# MorsePlay_schematic.net
KiCad netlist of a schematic drawn in EAGLE
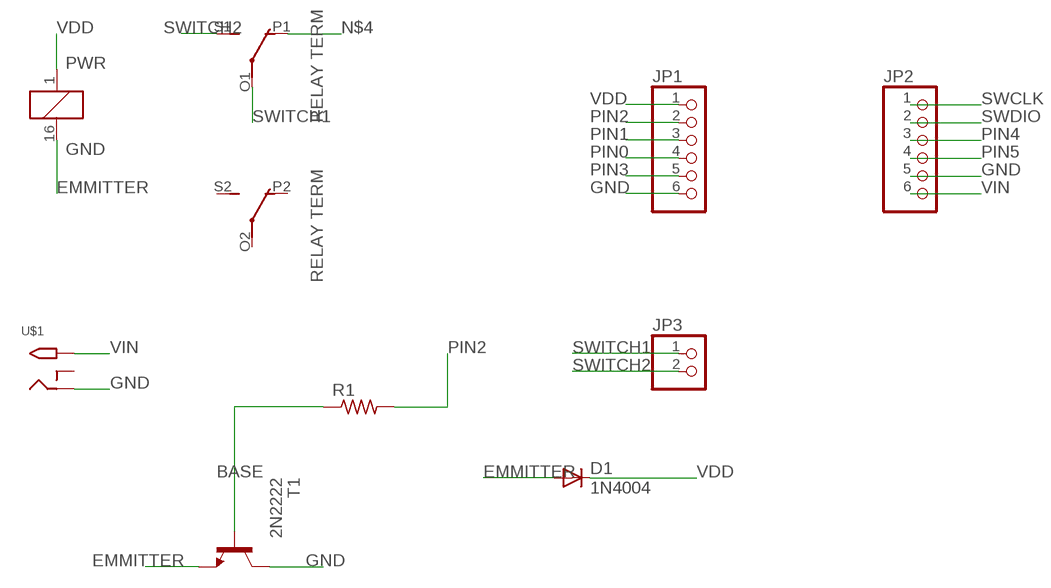
[diagram p0: schematic, sheet 1]

(export (version "E")
  (design (tool "Eeschema 10.0.6"))
  (components
    (comp (ref "D1")
      (value "1N4004")
      (footprint "eagle-import:DO41-10")
      (libsource (lib "eagle-import") (part "1N4004"))
    )
    (comp (ref "JP1")
      (value "PINHD-1X6")
      (footprint "eagle-import:1X06")
      (libsource (lib "eagle-import") (part "PINHD-1X6"))
    )
    (comp (ref "JP2")
      (value "PINHD-1X6")
      (footprint "eagle-import:1X06")
      (libsource (lib "eagle-import") (part "PINHD-1X6"))
    )
    (comp (ref "JP3")
      (value "PINHD-1X2")
      (footprint "eagle-import:1X02")
      (libsource (lib "eagle-import") (part "PINHD-1X2"))
    )
    (comp (ref "R1")
      (value "R-US_0204/7")
      (footprint "eagle-import:0204_7")
      (libsource (lib "eagle-import") (part "R-US_0204/7"))
    )
    (comp (ref "RELAY1")
      (value "RELAY_3VTERMINAL")
      (footprint "eagle-import:351")
      (libsource (lib "eagle-import") (part "RELAY_3VTERMINAL"))
    )
    (comp (ref "T1")
      (value "2N2222")
      (footprint "eagle-import:TO92-EBC-OVAL")
      (libsource (lib "eagle-import") (part "2N2222"))
    )
    (comp (ref "U$1")
      (value "DCPOWERJACK")
      (footprint "eagle-import:DCJACK_2MM_PTH")
      (libsource (lib "eagle-import") (part "DCPOWERJACK"))
    )
  )
  (nets
    (net (code "1") (name "/BASE") (class "Default")
      (node (ref "R1") (pin "1") (pinfunction "1_1") (pintype "passive"))
      (node (ref "T1") (pin "B") (pinfunction "B_B") (pintype "passive"))
    )
    (net (code "2") (name "/EMMITTER") (class "Default")
      (node (ref "D1") (pin "A") (pinfunction "A_A") (pintype "passive"))
      (node (ref "RELAY1") (pin "16") (pinfunction "GND_16") (pintype "passive"))
      (node (ref "T1") (pin "E") (pinfunction "E_E") (pintype "passive"))
    )
    (net (code "3") (name "/GND") (class "Default")
      (node (ref "JP1") (pin "6") (pinfunction "6_6") (pintype "passive"))
      (node (ref "JP2") (pin "5") (pinfunction "5_5") (pintype "passive"))
      (node (ref "T1") (pin "C") (pinfunction "C_C") (pintype "passive"))
      (node (ref "U$1") (pin "GND") (pinfunction "RING_GND") (pintype "bidirectional"))
    )
    (net (code "4") (name "/N$4") (class "Default")
      (node (ref "RELAY1") (pin "P1") (pinfunction "NC_P1") (pintype "passive"))
    )
    (net (code "5") (name "/PIN0") (class "Default")
      (node (ref "JP1") (pin "4") (pinfunction "4_4") (pintype "passive"))
    )
    (net (code "6") (name "/PIN1") (class "Default")
      (node (ref "JP1") (pin "3") (pinfunction "3_3") (pintype "passive"))
    )
    (net (code "7") (name "/PIN2") (class "Default")
      (node (ref "JP1") (pin "2") (pinfunction "2_2") (pintype "passive"))
      (node (ref "R1") (pin "2") (pinfunction "2_2") (pintype "passive"))
    )
    (net (code "8") (name "/PIN3") (class "Default")
      (node (ref "JP1") (pin "5") (pinfunction "5_5") (pintype "passive"))
    )
    (net (code "9") (name "/PIN4") (class "Default")
      (node (ref "JP2") (pin "3") (pinfunction "3_3") (pintype "passive"))
    )
    (net (code "10") (name "/PIN5") (class "Default")
      (node (ref "JP2") (pin "4") (pinfunction "4_4") (pintype "passive"))
    )
    (net (code "11") (name "/SWCLK") (class "Default")
      (node (ref "JP2") (pin "1") (pinfunction "1_1") (pintype "passive"))
    )
    (net (code "12") (name "/SWDIO") (class "Default")
      (node (ref "JP2") (pin "2") (pinfunction "2_2") (pintype "passive"))
    )
    (net (code "13") (name "/SWITCH1") (class "Default")
      (node (ref "JP3") (pin "1") (pinfunction "1_1") (pintype "passive"))
      (node (ref "RELAY1") (pin "O1") (pinfunction "COM_O1") (pintype "passive"))
    )
    (net (code "14") (name "/SWITCH2") (class "Default")
      (node (ref "JP3") (pin "2") (pinfunction "2_2") (pintype "passive"))
      (node (ref "RELAY1") (pin "S1") (pinfunction "NO_S1") (pintype "passive"))
    )
    (net (code "15") (name "/VDD") (class "Default")
      (node (ref "D1") (pin "C") (pinfunction "C_C") (pintype "passive"))
      (node (ref "JP1") (pin "1") (pinfunction "1_1") (pintype "passive"))
      (node (ref "RELAY1") (pin "1") (pinfunction "PWR_1") (pintype "passive"))
    )
    (net (code "16") (name "/VIN") (class "Default")
      (node (ref "JP2") (pin "6") (pinfunction "6_6") (pintype "passive"))
      (node (ref "U$1") (pin "PWR") (pinfunction "TIP_PWR") (pintype "bidirectional"))
    )
    (net (code "17") (name "unconnected-(RELAY1B-COM-PadO2)") (class "Default")
      (node (ref "RELAY1") (pin "O2") (pinfunction "COM_O2") (pintype "passive"))
    )
    (net (code "18") (name "unconnected-(RELAY1B-NC-PadP2)") (class "Default")
      (node (ref "RELAY1") (pin "P2") (pinfunction "NC_P2") (pintype "passive"))
    )
    (net (code "19") (name "unconnected-(RELAY1B-NO-PadS2)") (class "Default")
      (node (ref "RELAY1") (pin "S2") (pinfunction "NO_S2") (pintype "passive"))
    )
    (net (code "20") (name "unconnected-(U$1-RING_SW-PadGNDBREAK)") (class "Default")
      (node (ref "U$1") (pin "GNDBREAK") (pinfunction "RING_SW_GNDBREAK") (pintype "bidirectional"))
    )
  )
)
